# board.net
KiCad netlist of a schematic drawn in EAGLE
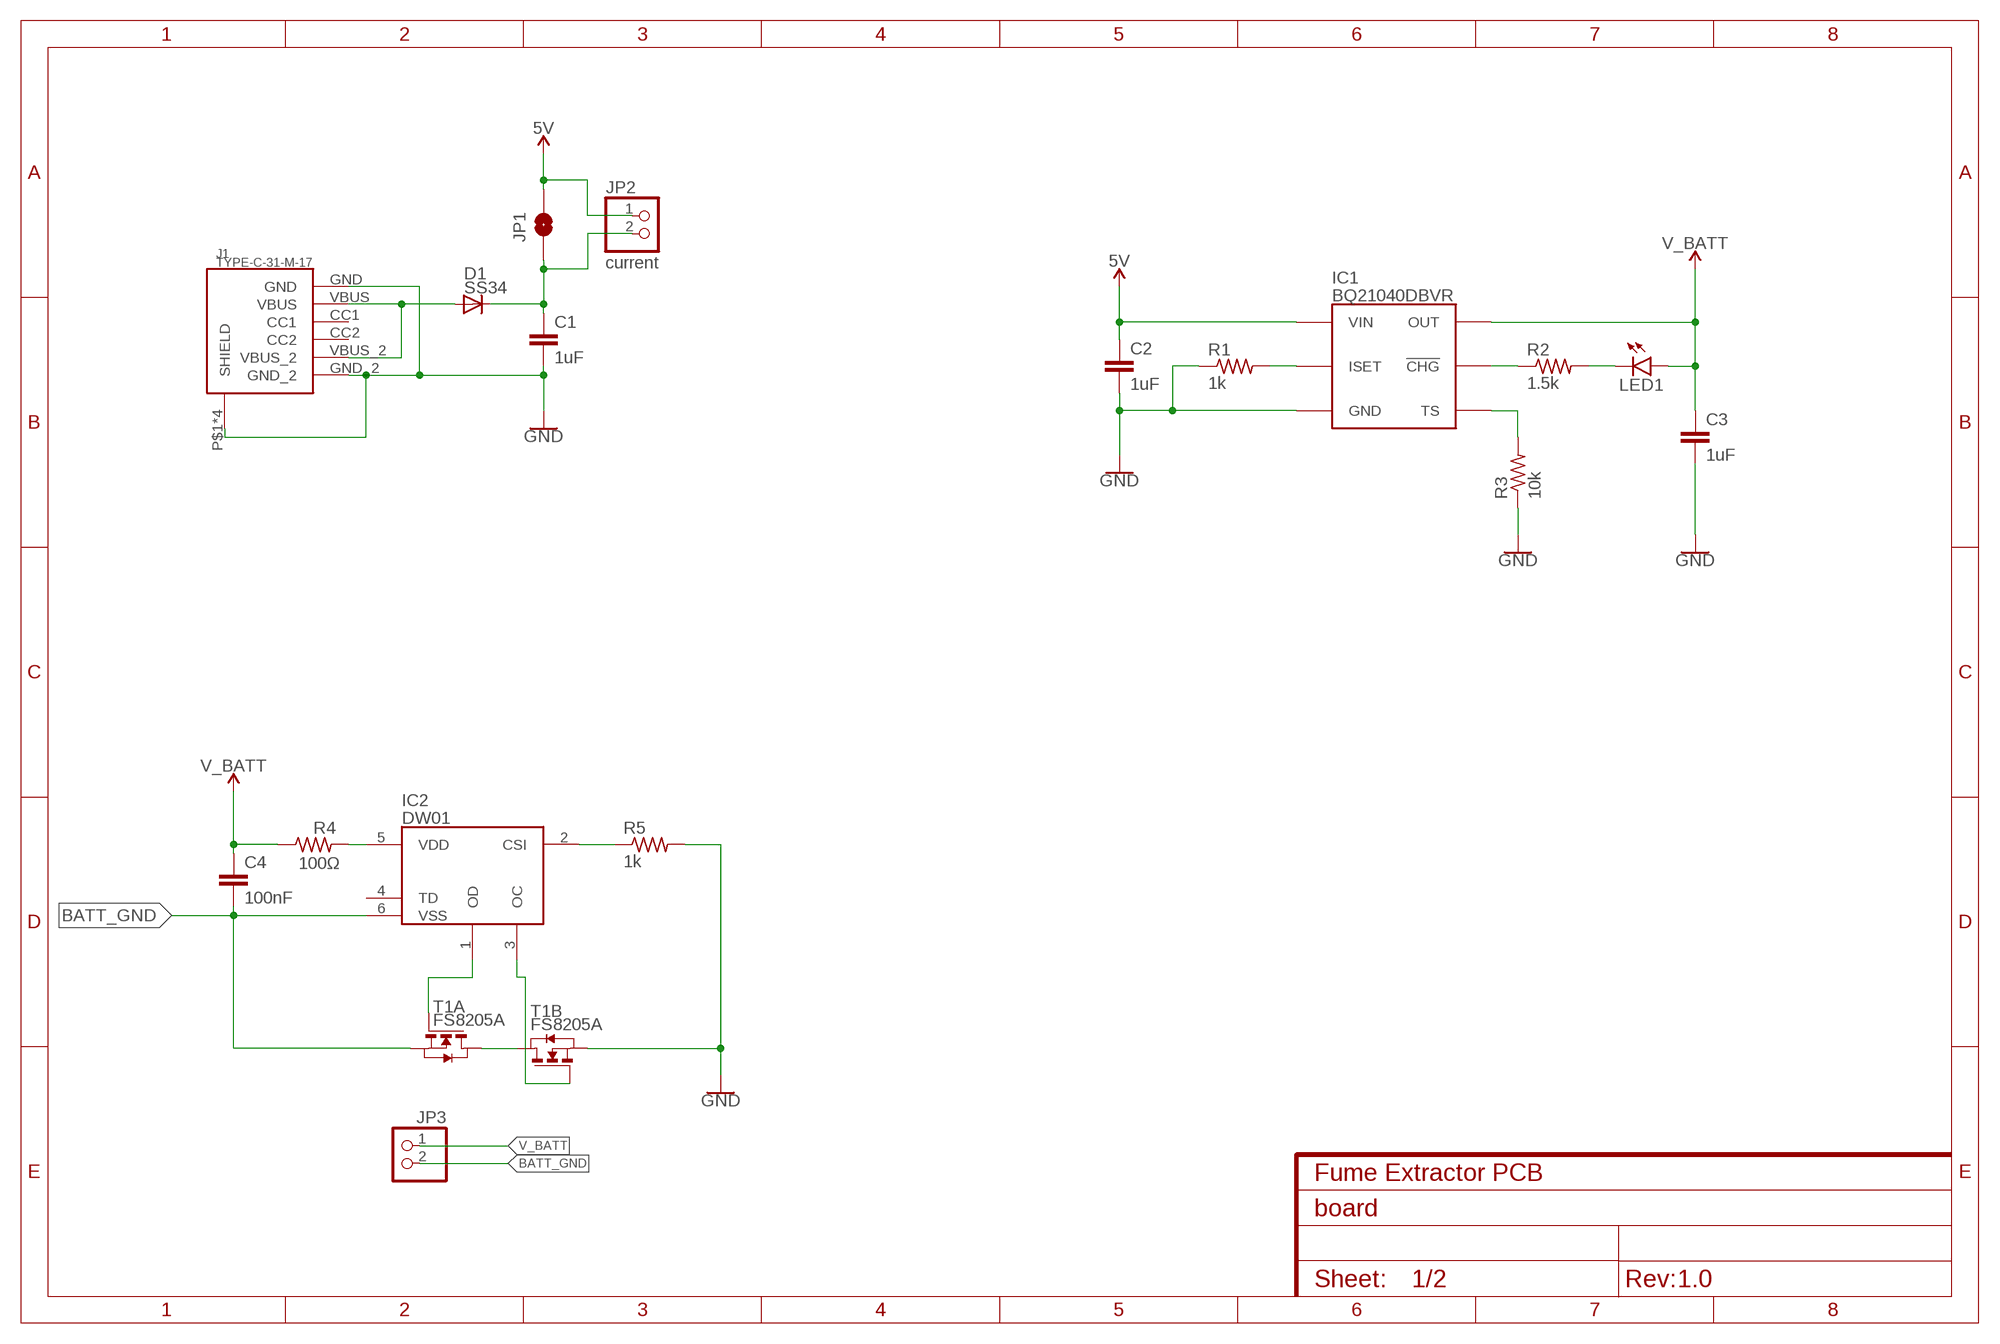
[diagram p0: schematic, sheet 1]
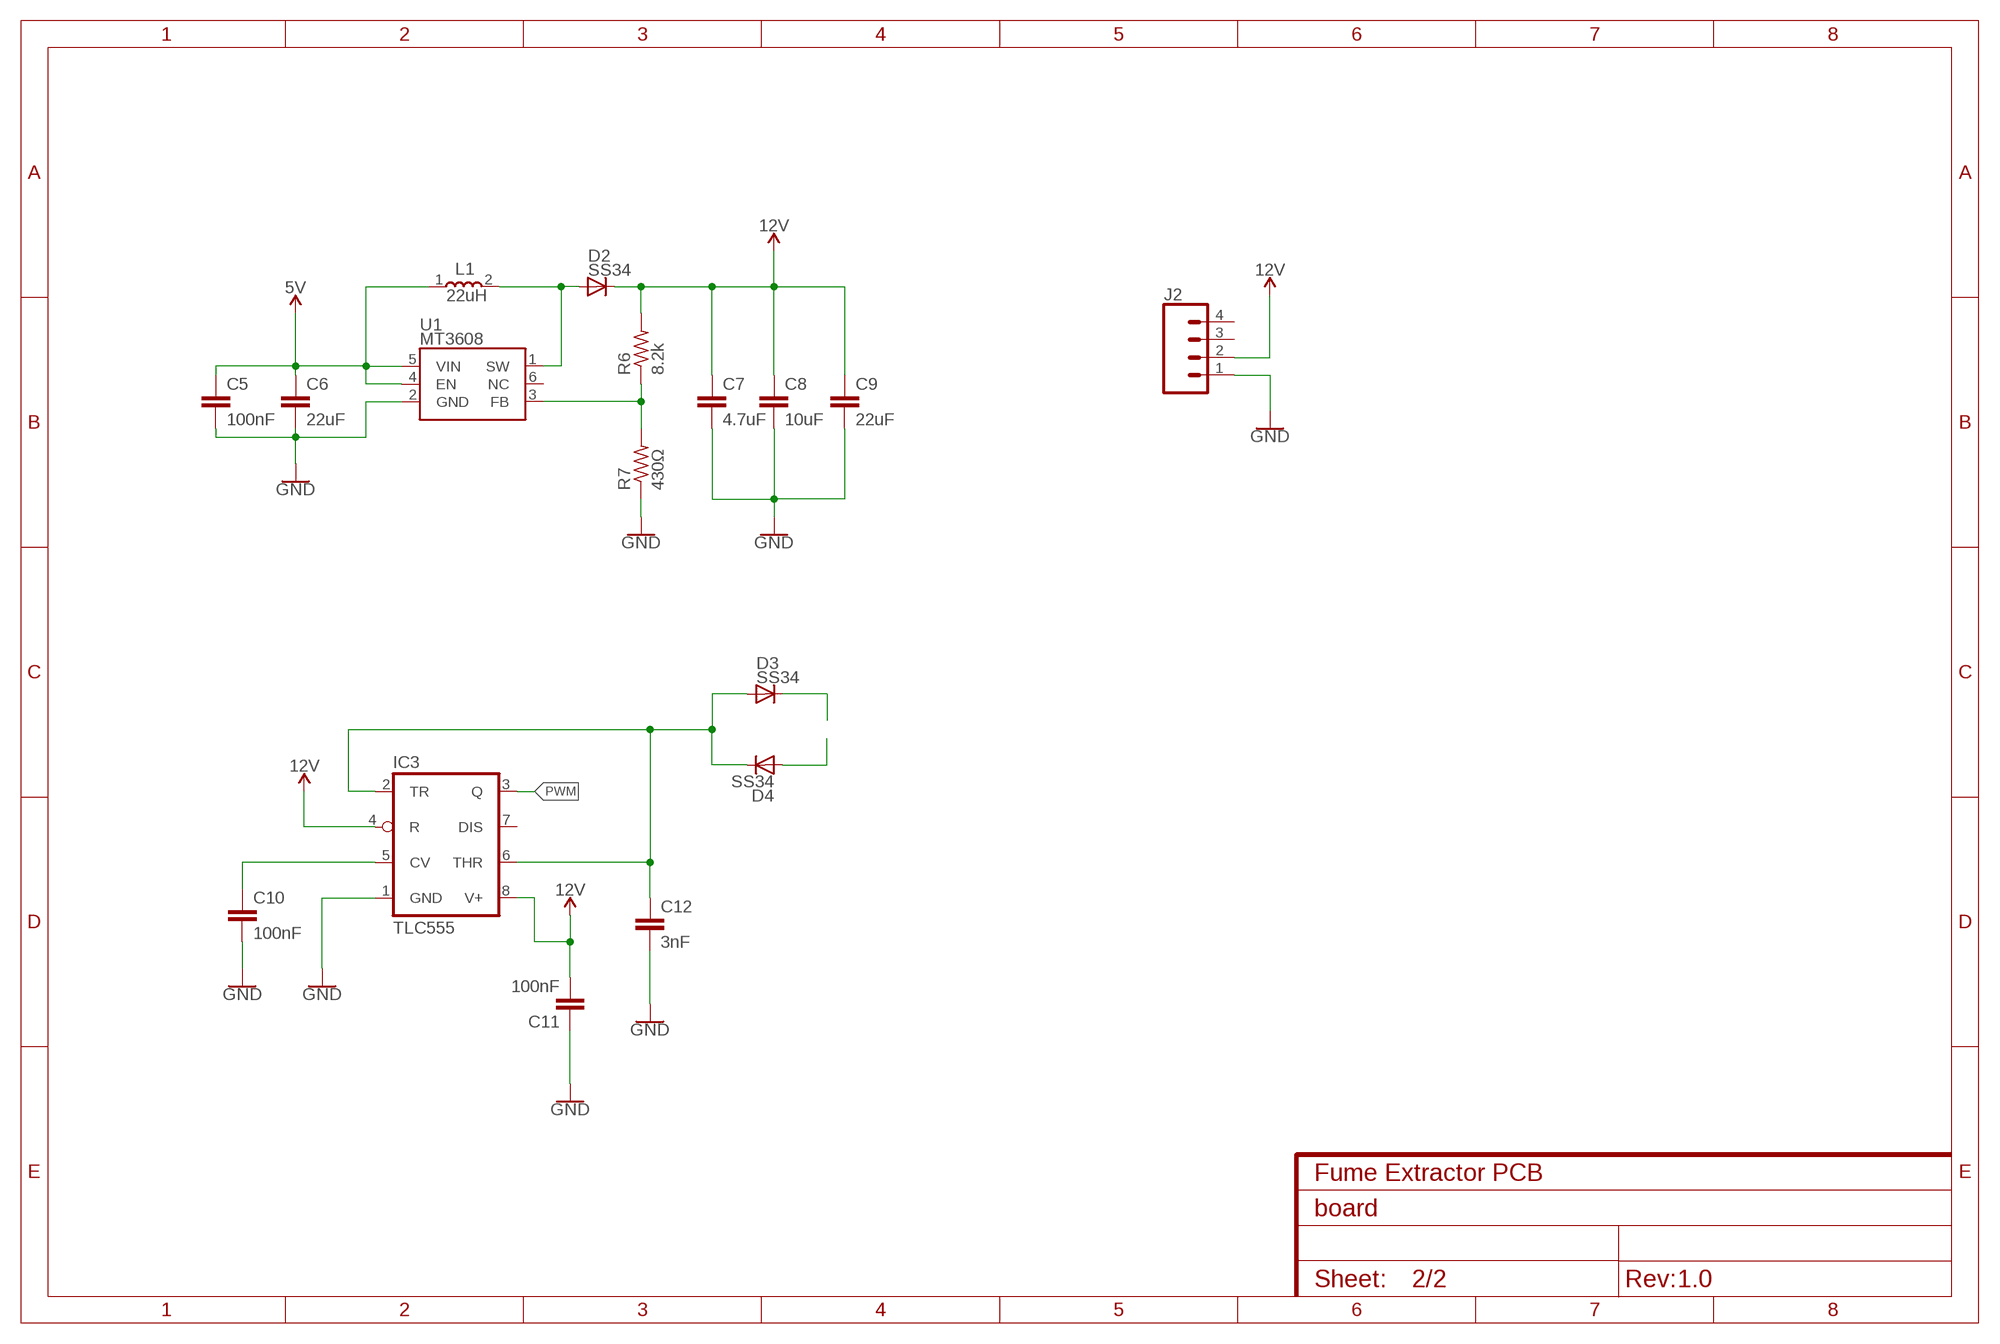
[diagram p1: schematic, sheet 2]

(export (version "E")
  (design (tool "Eeschema 10.0.6"))
  (components
    (comp (ref "C1")
      (value "1uF")
      (footprint "eagle-import:C0603")
      (libsource (lib "eagle-import") (part "C-EUC0603"))
    )
    (comp (ref "C2")
      (value "1uF")
      (footprint "eagle-import:C0603")
      (libsource (lib "eagle-import") (part "C-EUC0603"))
    )
    (comp (ref "C3")
      (value "1uF")
      (footprint "eagle-import:C0603")
      (libsource (lib "eagle-import") (part "C-EUC0603"))
    )
    (comp (ref "C4")
      (value "100nF")
      (footprint "eagle-import:C0603")
      (libsource (lib "eagle-import") (part "C-EUC0603"))
    )
    (comp (ref "D1")
      (value "SS34")
      (footprint "eagle-import:DO214AC")
      (libsource (lib "eagle-import") (part "DIODE-DO214AC"))
    )
    (comp (ref "IC1")
      (value "BQ21040DBVR")
      (footprint "eagle-import:SOT95P280X145-6N")
      (fields (field (name "MOUSER_PART_NUMBER") "595-BQ21040DBVR"))
      (libsource (lib "eagle-import") (part "BQ21040DBVR"))
    )
    (comp (ref "IC2")
      (value "DW01")
      (footprint "eagle-import:SOT95P280X135-6N")
      (libsource (lib "eagle-import") (part "DW01"))
    )
    (comp (ref "J1")
      (value "TYPE-C-31-M-17")
      (footprint "eagle-import:TYPE-C-31-M-17")
      (libsource (lib "eagle-import") (part "TYPE-C-31-M-17"))
    )
    (comp (ref "JP1")
      (value "JUMPER-SMT_2_NO_NO-SILK")
      (footprint "eagle-import:SMT-JUMPER_2_NO_NO-SILK")
      (libsource (lib "eagle-import") (part "JUMPER-SMT_2_NO_NO-SILK"))
    )
    (comp (ref "JP2")
      (value "current")
      (footprint "eagle-import:1X02_OCT")
      (libsource (lib "eagle-import") (part "PINHD-1X2/OCT"))
    )
    (comp (ref "JP3")
      (value "PINHD-1X2/OCT")
      (footprint "eagle-import:1X02_OCT")
      (libsource (lib "eagle-import") (part "PINHD-1X2/OCT"))
    )
    (comp (ref "LED1")
      (value "LEDCHIP-LED0805")
      (footprint "eagle-import:CHIP-LED0805")
      (libsource (lib "eagle-import") (part "LEDCHIP-LED0805"))
    )
    (comp (ref "R1")
      (value "1k")
      (footprint "eagle-import:R0603")
      (libsource (lib "eagle-import") (part "R-US_R0603"))
    )
    (comp (ref "R2")
      (value "1.5k")
      (footprint "eagle-import:R0603")
      (libsource (lib "eagle-import") (part "R-US_R0603"))
    )
    (comp (ref "R3")
      (value "10k")
      (footprint "eagle-import:R0603")
      (libsource (lib "eagle-import") (part "R-US_R0603"))
    )
    (comp (ref "R4")
      (value "100Ω")
      (footprint "eagle-import:R0603")
      (libsource (lib "eagle-import") (part "R-US_R0603"))
    )
    (comp (ref "R5")
      (value "1k")
      (footprint "eagle-import:R0603")
      (libsource (lib "eagle-import") (part "R-US_R0603"))
    )
    (comp (ref "T1")
      (value "FS8205A")
      (footprint "eagle-import:TSSOP-8")
      (libsource (lib "eagle-import") (part "FS8205A-MOSFET"))
    )
    (comp (ref "C5")
      (value "100nF")
      (footprint "eagle-import:C0603")
      (libsource (lib "eagle-import") (part "C-EUC0603"))
    )
    (comp (ref "C6")
      (value "22uF")
      (footprint "eagle-import:C0805")
      (libsource (lib "eagle-import") (part "C-EUC0805"))
    )
    (comp (ref "C7")
      (value "4.7uF")
      (footprint "eagle-import:C0603")
      (libsource (lib "eagle-import") (part "C-EUC0603"))
    )
    (comp (ref "C8")
      (value "10uF")
      (footprint "eagle-import:C0805")
      (libsource (lib "eagle-import") (part "C-EUC0805"))
    )
    (comp (ref "C9")
      (value "22uF")
      (footprint "eagle-import:C0805")
      (libsource (lib "eagle-import") (part "C-EUC0805"))
    )
    (comp (ref "C10")
      (value "100nF")
      (footprint "eagle-import:C0603")
      (libsource (lib "eagle-import") (part "C-EUC0603"))
    )
    (comp (ref "C11")
      (value "100nF")
      (footprint "eagle-import:C0603")
      (libsource (lib "eagle-import") (part "C-EUC0603"))
    )
    (comp (ref "C12")
      (value "3nF")
      (footprint "eagle-import:C0603")
      (libsource (lib "eagle-import") (part "C-EUC0603"))
    )
    (comp (ref "D2")
      (value "SS34")
      (footprint "eagle-import:DO214AC")
      (libsource (lib "eagle-import") (part "DIODE-DO214AC"))
    )
    (comp (ref "D3")
      (value "SS34")
      (footprint "eagle-import:DO214AC")
      (libsource (lib "eagle-import") (part "DIODE-DO214AC"))
    )
    (comp (ref "D4")
      (value "SS34")
      (footprint "eagle-import:DO214AC")
      (libsource (lib "eagle-import") (part "DIODE-DO214AC"))
    )
    (comp (ref "IC3")
      (value "TLC555")
      (footprint "eagle-import:SO08")
      (libsource (lib "eagle-import") (part "555DNE"))
    )
    (comp (ref "J2")
      (value "CONN_04POLAR_LOCK")
      (footprint "eagle-import:MOLEX-1X4_LOCK")
      (libsource (lib "eagle-import") (part "CONN_04POLAR_LOCK"))
    )
    (comp (ref "L1")
      (value "22uH")
      (footprint "eagle-import:INDPM7066X300N")
      (fields (field (name "MANUFACTURER_PART_NUMBER") "BCIHP0730-220M"))
      (libsource (lib "eagle-import") (part "BCIHP0730-220M"))
    )
    (comp (ref "R6")
      (value "8.2k")
      (footprint "eagle-import:R0603")
      (libsource (lib "eagle-import") (part "R-US_R0603"))
    )
    (comp (ref "R7")
      (value "430Ω")
      (footprint "eagle-import:R0603")
      (libsource (lib "eagle-import") (part "R-US_R0603"))
    )
    (comp (ref "U1")
      (value "MT3608")
      (footprint "eagle-import:SOT23-6")
      (libsource (lib "eagle-import") (part "MT3608"))
    )
  )
  (nets
    (net (code "1") (name "5V") (class "Default")
      (node (ref "C2") (pin "1") (pinfunction "1_1") (pintype "passive"))
      (node (ref "C5") (pin "1") (pinfunction "1_1") (pintype "passive"))
      (node (ref "C6") (pin "1") (pinfunction "1_1") (pintype "passive"))
      (node (ref "IC1") (pin "6") (pinfunction "VIN_6") (pintype "input"))
      (node (ref "JP1") (pin "2") (pinfunction "2_2") (pintype "passive"))
      (node (ref "JP2") (pin "1") (pinfunction "1_1") (pintype "passive"))
      (node (ref "L1") (pin "1") (pinfunction "1_1") (pintype "bidirectional"))
      (node (ref "U1") (pin "4") (pinfunction "EN_4") (pintype "bidirectional"))
      (node (ref "U1") (pin "5") (pinfunction "VIN_5") (pintype "bidirectional"))
    )
    (net (code "2") (name "12V") (class "Default")
      (node (ref "C11") (pin "2") (pinfunction "2_2") (pintype "passive"))
      (node (ref "C7") (pin "1") (pinfunction "1_1") (pintype "passive"))
      (node (ref "C8") (pin "1") (pinfunction "1_1") (pintype "passive"))
      (node (ref "C9") (pin "1") (pinfunction "1_1") (pintype "passive"))
      (node (ref "D2") (pin "C") (pinfunction "C_C") (pintype "passive"))
      (node (ref "IC3") (pin "4") (pinfunction "R_4") (pintype "input"))
      (node (ref "IC3") (pin "8") (pinfunction "V+_8") (pintype "power_in"))
      (node (ref "J2") (pin "2") (pinfunction "2_2") (pintype "passive"))
      (node (ref "R6") (pin "2") (pinfunction "2_2") (pintype "passive"))
    )
    (net (code "3") (name "BATT_GND") (class "Default")
      (node (ref "C4") (pin "2") (pinfunction "2_2") (pintype "passive"))
      (node (ref "IC2") (pin "6") (pinfunction "VSS_6") (pintype "bidirectional"))
      (node (ref "JP3") (pin "2") (pinfunction "2_2") (pintype "passive"))
      (node (ref "T1") (pin "2") (pinfunction "S_2") (pintype "passive"))
      (node (ref "T1") (pin "3") (pinfunction "S_3") (pintype "passive"))
    )
    (net (code "4") (name "GND") (class "Default")
      (node (ref "C1") (pin "2") (pinfunction "2_2") (pintype "passive"))
      (node (ref "C10") (pin "2") (pinfunction "2_2") (pintype "passive"))
      (node (ref "C11") (pin "1") (pinfunction "1_1") (pintype "passive"))
      (node (ref "C12") (pin "2") (pinfunction "2_2") (pintype "passive"))
      (node (ref "C2") (pin "2") (pinfunction "2_2") (pintype "passive"))
      (node (ref "C3") (pin "2") (pinfunction "2_2") (pintype "passive"))
      (node (ref "C5") (pin "2") (pinfunction "2_2") (pintype "passive"))
      (node (ref "C6") (pin "2") (pinfunction "2_2") (pintype "passive"))
      (node (ref "C7") (pin "2") (pinfunction "2_2") (pintype "passive"))
      (node (ref "C8") (pin "2") (pinfunction "2_2") (pintype "passive"))
      (node (ref "C9") (pin "2") (pinfunction "2_2") (pintype "passive"))
      (node (ref "IC1") (pin "5") (pinfunction "GND_5") (pintype "power_in"))
      (node (ref "IC3") (pin "1") (pinfunction "GND_1") (pintype "power_in"))
      (node (ref "J1") (pin "GND") (pinfunction "GND_GND") (pintype "bidirectional"))
      (node (ref "J1") (pin "GND_2") (pinfunction "GND_2_GND_2") (pintype "bidirectional"))
      (node (ref "J1") (pin "P$1") (pinfunction "SHIELD_P$1") (pintype "bidirectional"))
      (node (ref "J1") (pin "P$2") (pinfunction "SHIELD_P$2") (pintype "bidirectional"))
      (node (ref "J1") (pin "P$3") (pinfunction "SHIELD_P$3") (pintype "bidirectional"))
      (node (ref "J1") (pin "P$4") (pinfunction "SHIELD_P$4") (pintype "bidirectional"))
      (node (ref "J2") (pin "1") (pinfunction "1_1") (pintype "passive"))
      (node (ref "R1") (pin "1") (pinfunction "1_1") (pintype "passive"))
      (node (ref "R3") (pin "1") (pinfunction "1_1") (pintype "passive"))
      (node (ref "R5") (pin "2") (pinfunction "2_2") (pintype "passive"))
      (node (ref "R7") (pin "1") (pinfunction "1_1") (pintype "passive"))
      (node (ref "T1") (pin "6") (pinfunction "S_6") (pintype "passive"))
      (node (ref "T1") (pin "7") (pinfunction "S_7") (pintype "passive"))
      (node (ref "U1") (pin "2") (pinfunction "GND_2") (pintype "bidirectional"))
    )
    (net (code "5") (name "Net-(C1-Pad1)") (class "Default")
      (node (ref "C1") (pin "1") (pinfunction "1_1") (pintype "passive"))
      (node (ref "D1") (pin "C") (pinfunction "C_C") (pintype "passive"))
      (node (ref "JP1") (pin "1") (pinfunction "1_1") (pintype "passive"))
      (node (ref "JP2") (pin "2") (pinfunction "2_2") (pintype "passive"))
    )
    (net (code "6") (name "Net-(D1-PadA)") (class "Default")
      (node (ref "D1") (pin "A") (pinfunction "A_A") (pintype "passive"))
      (node (ref "J1") (pin "VBUS") (pinfunction "VBUS_VBUS") (pintype "bidirectional"))
      (node (ref "J1") (pin "VBUS_2") (pinfunction "VBUS_2_VBUS_2") (pintype "bidirectional"))
    )
    (net (code "7") (name "Net-(IC1-ISET)") (class "Default")
      (node (ref "IC1") (pin "4") (pinfunction "ISET_4") (pintype "input"))
      (node (ref "R1") (pin "2") (pinfunction "2_2") (pintype "passive"))
    )
    (net (code "8") (name "Net-(IC1-TS)") (class "Default")
      (node (ref "IC1") (pin "1") (pinfunction "TS_1") (pintype "input"))
      (node (ref "R3") (pin "2") (pinfunction "2_2") (pintype "passive"))
    )
    (net (code "9") (name "Net-(IC1-~{CHG})") (class "Default")
      (node (ref "IC1") (pin "3") (pinfunction "~{CHG}_3") (pintype "output"))
      (node (ref "R2") (pin "1") (pinfunction "1_1") (pintype "passive"))
    )
    (net (code "10") (name "Net-(IC2-CSI)") (class "Default")
      (node (ref "IC2") (pin "2") (pinfunction "CSI_2") (pintype "bidirectional"))
      (node (ref "R5") (pin "1") (pinfunction "1_1") (pintype "passive"))
    )
    (net (code "11") (name "Net-(IC2-OC)") (class "Default")
      (node (ref "IC2") (pin "3") (pinfunction "OC_3") (pintype "bidirectional"))
      (node (ref "T1") (pin "5") (pinfunction "G_5") (pintype "passive"))
    )
    (net (code "12") (name "Net-(IC2-OD)") (class "Default")
      (node (ref "IC2") (pin "1") (pinfunction "OD_1") (pintype "bidirectional"))
      (node (ref "T1") (pin "4") (pinfunction "G_4") (pintype "passive"))
    )
    (net (code "13") (name "Net-(IC2-VDD)") (class "Default")
      (node (ref "IC2") (pin "5") (pinfunction "VDD_5") (pintype "bidirectional"))
      (node (ref "R4") (pin "2") (pinfunction "2_2") (pintype "passive"))
    )
    (net (code "14") (name "Net-(IC3-CV)") (class "Default")
      (node (ref "C10") (pin "1") (pinfunction "1_1") (pintype "passive"))
      (node (ref "IC3") (pin "5") (pinfunction "CV_5") (pintype "input"))
    )
    (net (code "15") (name "Net-(IC3-THR)") (class "Default")
      (node (ref "C12") (pin "1") (pinfunction "1_1") (pintype "passive"))
      (node (ref "D3") (pin "A") (pinfunction "A_A") (pintype "passive"))
      (node (ref "D4") (pin "C") (pinfunction "C_C") (pintype "passive"))
      (node (ref "IC3") (pin "2") (pinfunction "TR_2") (pintype "input"))
      (node (ref "IC3") (pin "6") (pinfunction "THR_6") (pintype "input"))
    )
    (net (code "16") (name "Net-(LED1-PadC)") (class "Default")
      (node (ref "LED1") (pin "C") (pinfunction "C_C") (pintype "passive"))
      (node (ref "R2") (pin "2") (pinfunction "2_2") (pintype "passive"))
    )
    (net (code "17") (name "Net-(T1A-D)") (class "Default")
      (node (ref "T1") (pin "1") (pinfunction "D_1") (pintype "passive"))
      (node (ref "T1") (pin "8") (pinfunction "D_8") (pintype "passive"))
    )
    (net (code "18") (name "Net-(U1-FB)") (class "Default")
      (node (ref "R6") (pin "1") (pinfunction "1_1") (pintype "passive"))
      (node (ref "R7") (pin "2") (pinfunction "2_2") (pintype "passive"))
      (node (ref "U1") (pin "3") (pinfunction "FB_3") (pintype "bidirectional"))
    )
    (net (code "19") (name "Net-(U1-SW)") (class "Default")
      (node (ref "D2") (pin "A") (pinfunction "A_A") (pintype "passive"))
      (node (ref "L1") (pin "2") (pinfunction "2_2") (pintype "bidirectional"))
      (node (ref "U1") (pin "1") (pinfunction "SW_1") (pintype "bidirectional"))
    )
    (net (code "20") (name "PWM") (class "Default")
      (node (ref "IC3") (pin "3") (pinfunction "Q_3") (pintype "output"))
    )
    (net (code "21") (name "V_BATT") (class "Default")
      (node (ref "C3") (pin "1") (pinfunction "1_1") (pintype "passive"))
      (node (ref "C4") (pin "1") (pinfunction "1_1") (pintype "passive"))
      (node (ref "IC1") (pin "2") (pinfunction "OUT_2") (pintype "output"))
      (node (ref "JP3") (pin "1") (pinfunction "1_1") (pintype "passive"))
      (node (ref "LED1") (pin "A") (pinfunction "A_A") (pintype "passive"))
      (node (ref "R4") (pin "1") (pinfunction "1_1") (pintype "passive"))
    )
    (net (code "22") (name "unconnected-(D3-PadC)") (class "Default")
      (node (ref "D3") (pin "C") (pinfunction "C_C") (pintype "passive"))
    )
    (net (code "23") (name "unconnected-(D4-PadA)") (class "Default")
      (node (ref "D4") (pin "A") (pinfunction "A_A") (pintype "passive"))
    )
    (net (code "24") (name "unconnected-(IC2-TD-Pad4)") (class "Default")
      (node (ref "IC2") (pin "4") (pinfunction "TD_4") (pintype "bidirectional"))
    )
    (net (code "25") (name "unconnected-(IC3-DIS-Pad7)") (class "Default")
      (node (ref "IC3") (pin "7") (pinfunction "DIS_7") (pintype "input"))
    )
    (net (code "26") (name "unconnected-(J1-PadCC1)") (class "Default")
      (node (ref "J1") (pin "CC1") (pinfunction "CC1_CC1") (pintype "bidirectional"))
    )
    (net (code "27") (name "unconnected-(J1-PadCC2)") (class "Default")
      (node (ref "J1") (pin "CC2") (pinfunction "CC2_CC2") (pintype "bidirectional"))
    )
    (net (code "28") (name "unconnected-(J2-Pad3)") (class "Default")
      (node (ref "J2") (pin "3") (pinfunction "3_3") (pintype "passive"))
    )
    (net (code "29") (name "unconnected-(J2-Pad4)") (class "Default")
      (node (ref "J2") (pin "4") (pinfunction "4_4") (pintype "passive"))
    )
    (net (code "30") (name "unconnected-(U1-NC-Pad6)") (class "Default")
      (node (ref "U1") (pin "6") (pinfunction "NC_6") (pintype "bidirectional"))
    )
  )
)
